# input.net
KiCad netlist of a schematic drawn in Altium Designer
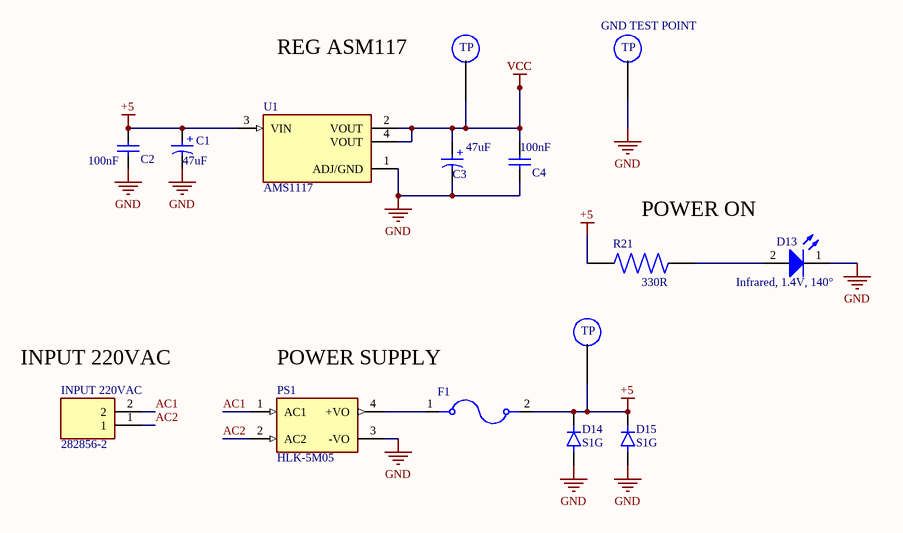
[diagram p0: input.SchDoc]

(export (version "E")
  (design (tool "Eeschema 10.0.6"))
  (components
    (comp (ref "5V")
      (value "TEST POINT")
      (footprint "TEST POINT")
      (libsource (lib "control") (part "TEST POINT"))
    )
    (comp (ref "C1")
      (value "47uF")
      (footprint "WCAP-ASLI_D6.3H7.7")
      (description "WCAP-ASLI Aluminum Electrolytic Capacitor, V-Chip, D6.3 x H5.5mm, 47uF, 25V")
      (fields
        (field (name "MANUFACTURER PART NUMBER") "865080443007")
        (field (name "MANUFACTURER") "Wurth Elektronik")
        (field (name "CAPACITANCE") "47uF")
      )
      (libsource (lib "input") (part "865080443007"))
    )
    (comp (ref "C2")
      (value "100nF")
      (footprint "WCAP-CSGP_0805_L2W1.25H0.8_Reflow")
      (description "WCAP-CSGP Multilayer Ceramic Chip Capacitor, General Purpose, size 0805, X7R, 100nF, 25VDC")
      (fields
        (field (name "MANUFACTURER PART NUMBER") "885012207072")
        (field (name "MANUFACTURER") "Wurth Elektronik")
      )
      (libsource (lib "input") (part "885012207072"))
    )
    (comp (ref "C3")
      (value "47uF")
      (footprint "WCAP-ASLI_D6.3H7.7")
      (description "WCAP-ASLI Aluminum Electrolytic Capacitor, V-Chip, D6.3 x H5.5mm, 47uF, 25V")
      (fields
        (field (name "MANUFACTURER PART NUMBER") "865080443007")
        (field (name "MANUFACTURER") "Wurth Elektronik")
        (field (name "CAPACITANCE") "47uF")
      )
      (libsource (lib "input") (part "865080443007"))
    )
    (comp (ref "C4")
      (value "100nF")
      (footprint "WCAP-CSGP_0805_L2W1.25H0.8_Reflow")
      (description "WCAP-CSGP Multilayer Ceramic Chip Capacitor, General Purpose, size 0805, X7R, 100nF, 25VDC")
      (fields
        (field (name "MANUFACTURER PART NUMBER") "885012207072")
        (field (name "MANUFACTURER") "Wurth Elektronik")
      )
      (libsource (lib "input") (part "885012207072"))
    )
    (comp (ref "D13")
      (value "Infrared, 1.4V, 140°")
      (footprint "WL-SICW_0805_L2W1.3H0.8")
      (description "WL-SICW SMT Chip LED Infrared Waterclear, size 0805, Infrared, 1.4V, 140°")
      (fields
        (field (name "MANUFACTURER PART NUMBER") "15408085BA400")
        (field (name "MANUFACTURER") "Wurth Elektronik")
      )
      (libsource (lib "input") (part "15408085BA400"))
    )
    (comp (ref "D14")
      (value "S1G")
      (footprint "DIO_S1G")
      (description "Diode Standard 400 V 1A Surface Mount DO-214AC (SMA)")
      (fields (field (name "MF") "ON Semiconductor"))
      (libsource (lib "input") (part "S1G"))
    )
    (comp (ref "D15")
      (value "S1G")
      (footprint "DIO_S1G")
      (description "Diode Standard 400 V 1A Surface Mount DO-214AC (SMA)")
      (fields (field (name "MF") "ON Semiconductor"))
      (libsource (lib "input") (part "S1G"))
    )
    (comp (ref "F1")
      (value "0154004.DR")
      (footprint "FUSE_0154004.DR:FUSE_0154004.DR")
      (description "154/154T/154L/154TL Series OMNI-BLOKÂ® Fuse and Holder Assembly")
      (libsource (lib "input") (part "0154004.DR"))
    )
    (comp (ref "GND")
      (value "TEST POINT")
      (footprint "TEST POINT")
      (libsource (lib "control") (part "TEST POINT"))
    )
    (comp (ref "INPUT 220VAC")
      (value "282856-2")
      (footprint "TE_282856-2")
      (description "TERMI-BLOK PCB MOUNT 2P")
      (fields (field (name "MF") "TE Connectivity"))
      (libsource (lib "input") (part "282856-2"))
    )
    (comp (ref "PS1")
      (value "HLK-5M05")
      (footprint "CONV_HLK-PM01")
      (description "AC DC 220V to 5V 5W 5Watt Isolated Switching Step-Down Power Supply Module Converter")
      (fields (field (name "MF") "Hi-link"))
      (libsource (lib "input") (part "HLK-5M05"))
    )
    (comp (ref "R21")
      (value "330R")
      (footprint "RESC3216X70N")
      (description "Res 1206 10 Ohm 5% 1/8W Â±500ppm/Â°C Molded SMD SMD T/R")
      (fields (field (name "TOLERANCE") "5%") (field (name "MP") "FCR1206J10R"))
      (libsource (lib "input") (part "FCR1206J10R"))
    )
    (comp (ref "U1")
      (value "AMS1117")
      (footprint "SOT229P700X180-4N")
      (description "1A LOW DROPOUT VOLTAGE REGULATOR SOT-223")
      (fields (field (name "MF") "Advanced Monolithic Systems"))
      (libsource (lib "input") (part "AMS1117"))
    )
    (comp (ref "VCC")
      (value "TEST POINT")
      (footprint "TEST POINT")
      (libsource (lib "control") (part "TEST POINT"))
    )
  )
  (nets
    (net (code "1") (name "+5") (class "Default")
      (node (ref "5V") (pin "1") (pinfunction "1_1") (pintype "passive"))
      (node (ref "C1") (pin "1") (pinfunction "P_1") (pintype "passive"))
      (node (ref "C2") (pin "2") (pinfunction "2_2") (pintype "passive"))
      (node (ref "D14") (pin "1") (pinfunction "K_1") (pintype "passive"))
      (node (ref "D15") (pin "1") (pinfunction "K_1") (pintype "passive"))
      (node (ref "F1") (pin "2") (pinfunction "2_2") (pintype "passive"))
      (node (ref "R21") (pin "1") (pinfunction "1_1") (pintype "passive"))
      (node (ref "U1") (pin "3") (pinfunction "VIN_3") (pintype "input"))
    )
    (net (code "2") (name "/AC1") (class "Default")
      (node (ref "INPUT 220VAC") (pin "2") (pinfunction "2_2") (pintype "passive"))
      (node (ref "PS1") (pin "1") (pinfunction "AC1_1") (pintype "input"))
    )
    (net (code "3") (name "/AC2") (class "Default")
      (node (ref "INPUT 220VAC") (pin "1") (pinfunction "1_1") (pintype "passive"))
      (node (ref "PS1") (pin "2") (pinfunction "AC2_2") (pintype "input"))
    )
    (net (code "4") (name "GND") (class "Default")
      (node (ref "C1") (pin "2") (pinfunction "N_2") (pintype "passive"))
      (node (ref "C2") (pin "1") (pinfunction "1_1") (pintype "passive"))
      (node (ref "C3") (pin "2") (pinfunction "N_2") (pintype "passive"))
      (node (ref "C4") (pin "1") (pinfunction "1_1") (pintype "passive"))
      (node (ref "D13") (pin "1") (pinfunction "K_1") (pintype "passive"))
      (node (ref "D14") (pin "2") (pinfunction "A_2") (pintype "passive"))
      (node (ref "D15") (pin "2") (pinfunction "A_2") (pintype "passive"))
      (node (ref "GND") (pin "1") (pinfunction "1_1") (pintype "passive"))
      (node (ref "PS1") (pin "3") (pinfunction "-VO_3") (pintype "power_in"))
      (node (ref "U1") (pin "1") (pinfunction "ADJ/GND_1") (pintype "power_in"))
    )
    (net (code "5") (name "Net-(D13-A)") (class "Default")
      (node (ref "D13") (pin "2") (pinfunction "A_2") (pintype "passive"))
      (node (ref "R21") (pin "2") (pinfunction "2_2") (pintype "passive"))
    )
    (net (code "6") (name "Net-(PS1-+VO)") (class "Default")
      (node (ref "F1") (pin "1") (pinfunction "1_1") (pintype "passive"))
      (node (ref "PS1") (pin "4") (pinfunction "+VO_4") (pintype "output"))
    )
    (net (code "7") (name "VCC") (class "Default")
      (node (ref "C3") (pin "1") (pinfunction "P_1") (pintype "passive"))
      (node (ref "C4") (pin "2") (pinfunction "2_2") (pintype "passive"))
      (node (ref "U1") (pin "2") (pinfunction "VOUT_2") (pintype "power_in"))
      (node (ref "U1") (pin "4") (pinfunction "VOUT_4") (pintype "power_in"))
      (node (ref "VCC") (pin "1") (pinfunction "1_1") (pintype "passive"))
    )
  )
)
